# RGB_FPGA_Misc.net
KiCad netlist of a schematic drawn in Altium Designer
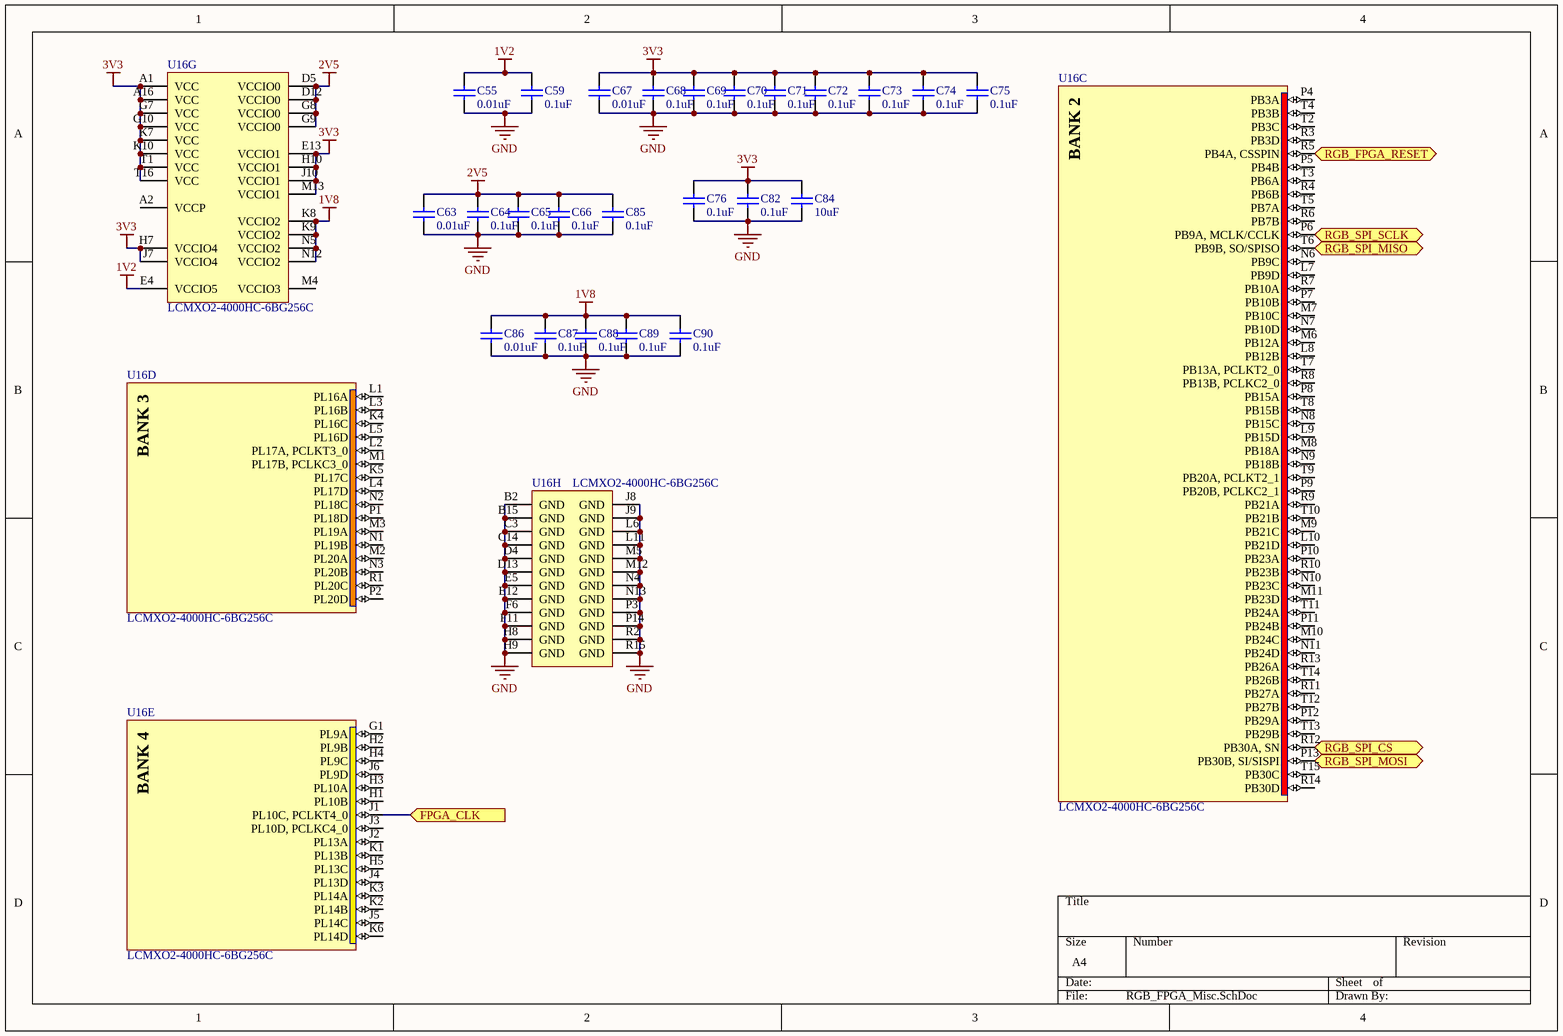
[diagram p0: RGB_FPGA_Misc.SchDoc]

(export (version "E")
  (design (tool "Eeschema 10.0.6"))
  (components
    (comp (ref "C55")
      (value "0.01uF")
      (footprint "0402C_M")
      (description "CAP CER 0.01uF 50V X7R 0402")
      (fields
        (field (name "MANUFACTURER") "Murata Electronics North America")
        (field (name "MANUFACTURER PART NUMBER") "GRM155R71H103KA88D")
      )
      (libsource (lib "KMTI-main") (part "GRM155R71H103KA88D"))
    )
    (comp (ref "C59")
      (value "GRM155R71C104KA88D")
      (footprint "0402C_M")
      (description "CAP CER 0.1UF 16V X7R 0402")
      (fields
        (field (name "MANUFACTURER") "Murata Electronics North America")
        (field (name "TOLERANCE") "±10%")
        (field (name "CAPACITANCE") "0.1uF")
      )
      (libsource (lib "KMTI-main") (part "GRM155R71C104KA88D"))
    )
    (comp (ref "C63")
      (value "0.01uF")
      (footprint "0402C_M")
      (description "CAP CER 0.01uF 50V X7R 0402")
      (fields
        (field (name "MANUFACTURER") "Murata Electronics North America")
        (field (name "MANUFACTURER PART NUMBER") "GRM155R71H103KA88D")
      )
      (libsource (lib "KMTI-main") (part "GRM155R71H103KA88D"))
    )
    (comp (ref "C64")
      (value "GRM155R71C104KA88D")
      (footprint "0402C_M")
      (description "CAP CER 0.1UF 16V X7R 0402")
      (fields
        (field (name "MANUFACTURER") "Murata Electronics North America")
        (field (name "TOLERANCE") "±10%")
        (field (name "CAPACITANCE") "0.1uF")
      )
      (libsource (lib "KMTI-main") (part "GRM155R71C104KA88D"))
    )
    (comp (ref "C65")
      (value "GRM155R71C104KA88D")
      (footprint "0402C_M")
      (description "CAP CER 0.1UF 16V X7R 0402")
      (fields
        (field (name "MANUFACTURER") "Murata Electronics North America")
        (field (name "TOLERANCE") "±10%")
        (field (name "CAPACITANCE") "0.1uF")
      )
      (libsource (lib "KMTI-main") (part "GRM155R71C104KA88D"))
    )
    (comp (ref "C66")
      (value "GRM155R71C104KA88D")
      (footprint "0402C_M")
      (description "CAP CER 0.1UF 16V X7R 0402")
      (fields
        (field (name "MANUFACTURER") "Murata Electronics North America")
        (field (name "TOLERANCE") "±10%")
        (field (name "CAPACITANCE") "0.1uF")
      )
      (libsource (lib "KMTI-main") (part "GRM155R71C104KA88D"))
    )
    (comp (ref "C67")
      (value "0.01uF")
      (footprint "0402C_M")
      (description "CAP CER 0.01uF 50V X7R 0402")
      (fields
        (field (name "MANUFACTURER") "Murata Electronics North America")
        (field (name "MANUFACTURER PART NUMBER") "GRM155R71H103KA88D")
      )
      (libsource (lib "KMTI-main") (part "GRM155R71H103KA88D"))
    )
    (comp (ref "C68")
      (value "GRM155R71C104KA88D")
      (footprint "0402C_M")
      (description "CAP CER 0.1UF 16V X7R 0402")
      (fields
        (field (name "MANUFACTURER") "Murata Electronics North America")
        (field (name "TOLERANCE") "±10%")
        (field (name "CAPACITANCE") "0.1uF")
      )
      (libsource (lib "KMTI-main") (part "GRM155R71C104KA88D"))
    )
    (comp (ref "C69")
      (value "GRM155R71C104KA88D")
      (footprint "0402C_M")
      (description "CAP CER 0.1UF 16V X7R 0402")
      (fields
        (field (name "MANUFACTURER") "Murata Electronics North America")
        (field (name "TOLERANCE") "±10%")
        (field (name "CAPACITANCE") "0.1uF")
      )
      (libsource (lib "KMTI-main") (part "GRM155R71C104KA88D"))
    )
    (comp (ref "C70")
      (value "GRM155R71C104KA88D")
      (footprint "0402C_M")
      (description "CAP CER 0.1UF 16V X7R 0402")
      (fields
        (field (name "MANUFACTURER") "Murata Electronics North America")
        (field (name "TOLERANCE") "±10%")
        (field (name "CAPACITANCE") "0.1uF")
      )
      (libsource (lib "KMTI-main") (part "GRM155R71C104KA88D"))
    )
    (comp (ref "C71")
      (value "GRM155R71C104KA88D")
      (footprint "0402C_M")
      (description "CAP CER 0.1UF 16V X7R 0402")
      (fields
        (field (name "MANUFACTURER") "Murata Electronics North America")
        (field (name "TOLERANCE") "±10%")
        (field (name "CAPACITANCE") "0.1uF")
      )
      (libsource (lib "KMTI-main") (part "GRM155R71C104KA88D"))
    )
    (comp (ref "C72")
      (value "GRM155R71C104KA88D")
      (footprint "0402C_M")
      (description "CAP CER 0.1UF 16V X7R 0402")
      (fields
        (field (name "MANUFACTURER") "Murata Electronics North America")
        (field (name "TOLERANCE") "±10%")
        (field (name "CAPACITANCE") "0.1uF")
      )
      (libsource (lib "KMTI-main") (part "GRM155R71C104KA88D"))
    )
    (comp (ref "C73")
      (value "GRM155R71C104KA88D")
      (footprint "0402C_M")
      (description "CAP CER 0.1UF 16V X7R 0402")
      (fields
        (field (name "MANUFACTURER") "Murata Electronics North America")
        (field (name "TOLERANCE") "±10%")
        (field (name "CAPACITANCE") "0.1uF")
      )
      (libsource (lib "KMTI-main") (part "GRM155R71C104KA88D"))
    )
    (comp (ref "C74")
      (value "GRM155R71C104KA88D")
      (footprint "0402C_M")
      (description "CAP CER 0.1UF 16V X7R 0402")
      (fields
        (field (name "MANUFACTURER") "Murata Electronics North America")
        (field (name "TOLERANCE") "±10%")
        (field (name "CAPACITANCE") "0.1uF")
      )
      (libsource (lib "KMTI-main") (part "GRM155R71C104KA88D"))
    )
    (comp (ref "C75")
      (value "GRM155R71C104KA88D")
      (footprint "0402C_M")
      (description "CAP CER 0.1UF 16V X7R 0402")
      (fields
        (field (name "MANUFACTURER") "Murata Electronics North America")
        (field (name "TOLERANCE") "±10%")
        (field (name "CAPACITANCE") "0.1uF")
      )
      (libsource (lib "KMTI-main") (part "GRM155R71C104KA88D"))
    )
    (comp (ref "C76")
      (value "GRM155R71C104KA88D")
      (footprint "0402C_M")
      (description "CAP CER 0.1UF 16V X7R 0402")
      (fields
        (field (name "MANUFACTURER") "Murata Electronics North America")
        (field (name "TOLERANCE") "±10%")
        (field (name "CAPACITANCE") "0.1uF")
      )
      (libsource (lib "KMTI-main") (part "GRM155R71C104KA88D"))
    )
    (comp (ref "C82")
      (value "GRM155R71C104KA88D")
      (footprint "0402C_M")
      (description "CAP CER 0.1UF 16V X7R 0402")
      (fields
        (field (name "MANUFACTURER") "Murata Electronics North America")
        (field (name "TOLERANCE") "±10%")
        (field (name "CAPACITANCE") "0.1uF")
      )
      (libsource (lib "KMTI-main") (part "GRM155R71C104KA88D"))
    )
    (comp (ref "C84")
      (value "10uF")
      (footprint "0603C_M")
      (description "CAP CER 10UF 6.3V X5R 0603")
      (fields
        (field (name "MANUFACTURER") "Murata Electronics North America")
        (field (name "MANUFACTURER PART NUMBER") "GRM188R60J106ME47D")
      )
      (libsource (lib "KMTI-main") (part "GRM188R60J106ME47D"))
    )
    (comp (ref "C85")
      (value "GRM155R71C104KA88D")
      (footprint "0402C_M")
      (description "CAP CER 0.1UF 16V X7R 0402")
      (fields
        (field (name "MANUFACTURER") "Murata Electronics North America")
        (field (name "TOLERANCE") "±10%")
        (field (name "CAPACITANCE") "0.1uF")
      )
      (libsource (lib "KMTI-main") (part "GRM155R71C104KA88D"))
    )
    (comp (ref "C86")
      (value "0.01uF")
      (footprint "0402C_M")
      (description "CAP CER 0.01uF 50V X7R 0402")
      (fields
        (field (name "MANUFACTURER") "Murata Electronics North America")
        (field (name "MANUFACTURER PART NUMBER") "GRM155R71H103KA88D")
      )
      (libsource (lib "KMTI-main") (part "GRM155R71H103KA88D"))
    )
    (comp (ref "C87")
      (value "GRM155R71C104KA88D")
      (footprint "0402C_M")
      (description "CAP CER 0.1UF 16V X7R 0402")
      (fields
        (field (name "MANUFACTURER") "Murata Electronics North America")
        (field (name "TOLERANCE") "±10%")
        (field (name "CAPACITANCE") "0.1uF")
      )
      (libsource (lib "KMTI-main") (part "GRM155R71C104KA88D"))
    )
    (comp (ref "C88")
      (value "GRM155R71C104KA88D")
      (footprint "0402C_M")
      (description "CAP CER 0.1UF 16V X7R 0402")
      (fields
        (field (name "MANUFACTURER") "Murata Electronics North America")
        (field (name "TOLERANCE") "±10%")
        (field (name "CAPACITANCE") "0.1uF")
      )
      (libsource (lib "KMTI-main") (part "GRM155R71C104KA88D"))
    )
    (comp (ref "C89")
      (value "GRM155R71C104KA88D")
      (footprint "0402C_M")
      (description "CAP CER 0.1UF 16V X7R 0402")
      (fields
        (field (name "MANUFACTURER") "Murata Electronics North America")
        (field (name "TOLERANCE") "±10%")
        (field (name "CAPACITANCE") "0.1uF")
      )
      (libsource (lib "KMTI-main") (part "GRM155R71C104KA88D"))
    )
    (comp (ref "C90")
      (value "GRM155R71C104KA88D")
      (footprint "0402C_M")
      (description "CAP CER 0.1UF 16V X7R 0402")
      (fields
        (field (name "MANUFACTURER") "Murata Electronics North America")
        (field (name "TOLERANCE") "±10%")
        (field (name "CAPACITANCE") "0.1uF")
      )
      (libsource (lib "KMTI-main") (part "GRM155R71C104KA88D"))
    )
    (comp (ref "U16")
      (value "LCMXO2-4000HC-6BG256C")
      (footprint "caBGA256")
      (libsource (lib "Altium Content Vault") (part "PLD-LTMXO2-4000-GA256"))
    )
  )
  (nets
    (net (code "1") (name "/FPGA_CLK") (class "Default")
      (node (ref "U16") (pin "J1") (pinfunction "PL10C,_PCLKT4_0_J1") (pintype "bidirectional"))
    )
    (net (code "2") (name "/RGB_FPGA_RESET") (class "Default")
      (node (ref "U16") (pin "R5") (pinfunction "PB4A,_CSSPIN_R5") (pintype "bidirectional"))
    )
    (net (code "3") (name "/RGB_SPI_CS") (class "Default")
      (node (ref "U16") (pin "R12") (pinfunction "PB30A,_SN_R12") (pintype "bidirectional"))
    )
    (net (code "4") (name "/RGB_SPI_MISO") (class "Default")
      (node (ref "U16") (pin "T6") (pinfunction "PB9B,_SO/SPISO_T6") (pintype "bidirectional"))
    )
    (net (code "5") (name "/RGB_SPI_MOSI") (class "Default")
      (node (ref "U16") (pin "P13") (pinfunction "PB30B,_SI/SISPI_P13") (pintype "bidirectional"))
    )
    (net (code "6") (name "/RGB_SPI_SCLK") (class "Default")
      (node (ref "U16") (pin "P6") (pinfunction "PB9A,_MCLK/CCLK_P6") (pintype "bidirectional"))
    )
    (net (code "7") (name "1V2") (class "Default")
      (node (ref "C55") (pin "2") (pinfunction "2_2") (pintype "passive"))
      (node (ref "C59") (pin "2") (pinfunction "2_2") (pintype "passive"))
      (node (ref "U16") (pin "E4") (pinfunction "VCCIO5_E4") (pintype "power_in"))
    )
    (net (code "8") (name "1V8") (class "Default")
      (node (ref "C86") (pin "2") (pinfunction "2_2") (pintype "passive"))
      (node (ref "C87") (pin "2") (pinfunction "2_2") (pintype "passive"))
      (node (ref "C88") (pin "2") (pinfunction "2_2") (pintype "passive"))
      (node (ref "C89") (pin "2") (pinfunction "2_2") (pintype "passive"))
      (node (ref "C90") (pin "2") (pinfunction "2_2") (pintype "passive"))
      (node (ref "U16") (pin "K8") (pinfunction "VCCIO2_K8") (pintype "power_in"))
      (node (ref "U16") (pin "K9") (pinfunction "VCCIO2_K9") (pintype "power_in"))
      (node (ref "U16") (pin "N12") (pinfunction "VCCIO2_N12") (pintype "power_in"))
      (node (ref "U16") (pin "N5") (pinfunction "VCCIO2_N5") (pintype "power_in"))
    )
    (net (code "9") (name "2V5") (class "Default")
      (node (ref "C63") (pin "2") (pinfunction "2_2") (pintype "passive"))
      (node (ref "C64") (pin "2") (pinfunction "2_2") (pintype "passive"))
      (node (ref "C65") (pin "2") (pinfunction "2_2") (pintype "passive"))
      (node (ref "C66") (pin "2") (pinfunction "2_2") (pintype "passive"))
      (node (ref "C85") (pin "2") (pinfunction "2_2") (pintype "passive"))
      (node (ref "U16") (pin "D12") (pinfunction "VCCIO0_D12") (pintype "power_in"))
      (node (ref "U16") (pin "D5") (pinfunction "VCCIO0_D5") (pintype "power_in"))
      (node (ref "U16") (pin "G8") (pinfunction "VCCIO0_G8") (pintype "power_in"))
      (node (ref "U16") (pin "G9") (pinfunction "VCCIO0_G9") (pintype "power_in"))
    )
    (net (code "10") (name "3V3") (class "Default")
      (node (ref "C67") (pin "2") (pinfunction "2_2") (pintype "passive"))
      (node (ref "C68") (pin "2") (pinfunction "2_2") (pintype "passive"))
      (node (ref "C69") (pin "2") (pinfunction "2_2") (pintype "passive"))
      (node (ref "C70") (pin "2") (pinfunction "2_2") (pintype "passive"))
      (node (ref "C71") (pin "2") (pinfunction "2_2") (pintype "passive"))
      (node (ref "C72") (pin "2") (pinfunction "2_2") (pintype "passive"))
      (node (ref "C73") (pin "2") (pinfunction "2_2") (pintype "passive"))
      (node (ref "C74") (pin "2") (pinfunction "2_2") (pintype "passive"))
      (node (ref "C75") (pin "2") (pinfunction "2_2") (pintype "passive"))
      (node (ref "C76") (pin "2") (pinfunction "2_2") (pintype "passive"))
      (node (ref "C82") (pin "2") (pinfunction "2_2") (pintype "passive"))
      (node (ref "C84") (pin "2") (pinfunction "2_2") (pintype "passive"))
      (node (ref "U16") (pin "A1") (pinfunction "VCC_A1") (pintype "power_in"))
      (node (ref "U16") (pin "A16") (pinfunction "VCC_A16") (pintype "power_in"))
      (node (ref "U16") (pin "E13") (pinfunction "VCCIO1_E13") (pintype "power_in"))
      (node (ref "U16") (pin "G10") (pinfunction "VCC_G10") (pintype "power_in"))
      (node (ref "U16") (pin "G7") (pinfunction "VCC_G7") (pintype "power_in"))
      (node (ref "U16") (pin "H10") (pinfunction "VCCIO1_H10") (pintype "power_in"))
      (node (ref "U16") (pin "H7") (pinfunction "VCCIO4_H7") (pintype "power_in"))
      (node (ref "U16") (pin "J10") (pinfunction "VCCIO1_J10") (pintype "power_in"))
      (node (ref "U16") (pin "J7") (pinfunction "VCCIO4_J7") (pintype "power_in"))
      (node (ref "U16") (pin "K10") (pinfunction "VCC_K10") (pintype "power_in"))
      (node (ref "U16") (pin "K7") (pinfunction "VCC_K7") (pintype "power_in"))
      (node (ref "U16") (pin "M13") (pinfunction "VCCIO1_M13") (pintype "power_in"))
      (node (ref "U16") (pin "T1") (pinfunction "VCC_T1") (pintype "power_in"))
      (node (ref "U16") (pin "T16") (pinfunction "VCC_T16") (pintype "power_in"))
    )
    (net (code "11") (name "GND") (class "Default")
      (node (ref "C55") (pin "1") (pinfunction "1_1") (pintype "passive"))
      (node (ref "C59") (pin "1") (pinfunction "1_1") (pintype "passive"))
      (node (ref "C63") (pin "1") (pinfunction "1_1") (pintype "passive"))
      (node (ref "C64") (pin "1") (pinfunction "1_1") (pintype "passive"))
      (node (ref "C65") (pin "1") (pinfunction "1_1") (pintype "passive"))
      (node (ref "C66") (pin "1") (pinfunction "1_1") (pintype "passive"))
      (node (ref "C67") (pin "1") (pinfunction "1_1") (pintype "passive"))
      (node (ref "C68") (pin "1") (pinfunction "1_1") (pintype "passive"))
      (node (ref "C69") (pin "1") (pinfunction "1_1") (pintype "passive"))
      (node (ref "C70") (pin "1") (pinfunction "1_1") (pintype "passive"))
      (node (ref "C71") (pin "1") (pinfunction "1_1") (pintype "passive"))
      (node (ref "C72") (pin "1") (pinfunction "1_1") (pintype "passive"))
      (node (ref "C73") (pin "1") (pinfunction "1_1") (pintype "passive"))
      (node (ref "C74") (pin "1") (pinfunction "1_1") (pintype "passive"))
      (node (ref "C75") (pin "1") (pinfunction "1_1") (pintype "passive"))
      (node (ref "C76") (pin "1") (pinfunction "1_1") (pintype "passive"))
      (node (ref "C82") (pin "1") (pinfunction "1_1") (pintype "passive"))
      (node (ref "C84") (pin "1") (pinfunction "1_1") (pintype "passive"))
      (node (ref "C85") (pin "1") (pinfunction "1_1") (pintype "passive"))
      (node (ref "C86") (pin "1") (pinfunction "1_1") (pintype "passive"))
      (node (ref "C87") (pin "1") (pinfunction "1_1") (pintype "passive"))
      (node (ref "C88") (pin "1") (pinfunction "1_1") (pintype "passive"))
      (node (ref "C89") (pin "1") (pinfunction "1_1") (pintype "passive"))
      (node (ref "C90") (pin "1") (pinfunction "1_1") (pintype "passive"))
      (node (ref "U16") (pin "B15") (pinfunction "GND_B15") (pintype "power_in"))
      (node (ref "U16") (pin "B2") (pinfunction "GND_B2") (pintype "power_in"))
      (node (ref "U16") (pin "C14") (pinfunction "GND_C14") (pintype "power_in"))
      (node (ref "U16") (pin "C3") (pinfunction "GND_C3") (pintype "power_in"))
      (node (ref "U16") (pin "D13") (pinfunction "GND_D13") (pintype "power_in"))
      (node (ref "U16") (pin "D4") (pinfunction "GND_D4") (pintype "power_in"))
      (node (ref "U16") (pin "E12") (pinfunction "GND_E12") (pintype "power_in"))
      (node (ref "U16") (pin "E5") (pinfunction "GND_E5") (pintype "power_in"))
      (node (ref "U16") (pin "F11") (pinfunction "GND_F11") (pintype "power_in"))
      (node (ref "U16") (pin "F6") (pinfunction "GND_F6") (pintype "power_in"))
      (node (ref "U16") (pin "H8") (pinfunction "GND_H8") (pintype "power_in"))
      (node (ref "U16") (pin "H9") (pinfunction "GND_H9") (pintype "power_in"))
      (node (ref "U16") (pin "J8") (pinfunction "GND_J8") (pintype "power_in"))
      (node (ref "U16") (pin "J9") (pinfunction "GND_J9") (pintype "power_in"))
      (node (ref "U16") (pin "L11") (pinfunction "GND_L11") (pintype "power_in"))
      (node (ref "U16") (pin "L6") (pinfunction "GND_L6") (pintype "power_in"))
      (node (ref "U16") (pin "M12") (pinfunction "GND_M12") (pintype "power_in"))
      (node (ref "U16") (pin "M5") (pinfunction "GND_M5") (pintype "power_in"))
      (node (ref "U16") (pin "N13") (pinfunction "GND_N13") (pintype "power_in"))
      (node (ref "U16") (pin "N4") (pinfunction "GND_N4") (pintype "power_in"))
      (node (ref "U16") (pin "P14") (pinfunction "GND_P14") (pintype "power_in"))
      (node (ref "U16") (pin "P3") (pinfunction "GND_P3") (pintype "power_in"))
      (node (ref "U16") (pin "R15") (pinfunction "GND_R15") (pintype "power_in"))
      (node (ref "U16") (pin "R2") (pinfunction "GND_R2") (pintype "power_in"))
    )
    (net (code "12") (name "unconnected-(U16C-PB3A-PadP4)") (class "Default")
      (node (ref "U16") (pin "P4") (pinfunction "PB3A_P4") (pintype "bidirectional"))
    )
    (net (code "13") (name "unconnected-(U16C-PB3B-PadT4)") (class "Default")
      (node (ref "U16") (pin "T4") (pinfunction "PB3B_T4") (pintype "bidirectional"))
    )
    (net (code "14") (name "unconnected-(U16C-PB3C-PadT2)") (class "Default")
      (node (ref "U16") (pin "T2") (pinfunction "PB3C_T2") (pintype "bidirectional"))
    )
    (net (code "15") (name "unconnected-(U16C-PB3D-PadR3)") (class "Default")
      (node (ref "U16") (pin "R3") (pinfunction "PB3D_R3") (pintype "bidirectional"))
    )
    (net (code "16") (name "unconnected-(U16C-PB4B-PadP5)") (class "Default")
      (node (ref "U16") (pin "P5") (pinfunction "PB4B_P5") (pintype "bidirectional"))
    )
    (net (code "17") (name "unconnected-(U16C-PB6A-PadT3)") (class "Default")
      (node (ref "U16") (pin "T3") (pinfunction "PB6A_T3") (pintype "bidirectional"))
    )
    (net (code "18") (name "unconnected-(U16C-PB6B-PadR4)") (class "Default")
      (node (ref "U16") (pin "R4") (pinfunction "PB6B_R4") (pintype "bidirectional"))
    )
    (net (code "19") (name "unconnected-(U16C-PB7A-PadT5)") (class "Default")
      (node (ref "U16") (pin "T5") (pinfunction "PB7A_T5") (pintype "bidirectional"))
    )
    (net (code "20") (name "unconnected-(U16C-PB7B-PadR6)") (class "Default")
      (node (ref "U16") (pin "R6") (pinfunction "PB7B_R6") (pintype "bidirectional"))
    )
    (net (code "21") (name "unconnected-(U16C-PB9C-PadN6)") (class "Default")
      (node (ref "U16") (pin "N6") (pinfunction "PB9C_N6") (pintype "bidirectional"))
    )
    (net (code "22") (name "unconnected-(U16C-PB9D-PadL7)") (class "Default")
      (node (ref "U16") (pin "L7") (pinfunction "PB9D_L7") (pintype "bidirectional"))
    )
    (net (code "23") (name "unconnected-(U16C-PB10A-PadR7)") (class "Default")
      (node (ref "U16") (pin "R7") (pinfunction "PB10A_R7") (pintype "bidirectional"))
    )
    (net (code "24") (name "unconnected-(U16C-PB10B-PadP7)") (class "Default")
      (node (ref "U16") (pin "P7") (pinfunction "PB10B_P7") (pintype "bidirectional"))
    )
    (net (code "25") (name "unconnected-(U16C-PB10C-PadM7)") (class "Default")
      (node (ref "U16") (pin "M7") (pinfunction "PB10C_M7") (pintype "bidirectional"))
    )
    (net (code "26") (name "unconnected-(U16C-PB10D-PadN7)") (class "Default")
      (node (ref "U16") (pin "N7") (pinfunction "PB10D_N7") (pintype "bidirectional"))
    )
    (net (code "27") (name "unconnected-(U16C-PB12A-PadM6)") (class "Default")
      (node (ref "U16") (pin "M6") (pinfunction "PB12A_M6") (pintype "bidirectional"))
    )
    (net (code "28") (name "unconnected-(U16C-PB12B-PadL8)") (class "Default")
      (node (ref "U16") (pin "L8") (pinfunction "PB12B_L8") (pintype "bidirectional"))
    )
    (net (code "29") (name "unconnected-(U16C-PB13A,_PCLKT2_0-PadT7)") (class "Default")
      (node (ref "U16") (pin "T7") (pinfunction "PB13A,_PCLKT2_0_T7") (pintype "bidirectional"))
    )
    (net (code "30") (name "unconnected-(U16C-PB13B,_PCLKC2_0-PadR8)") (class "Default")
      (node (ref "U16") (pin "R8") (pinfunction "PB13B,_PCLKC2_0_R8") (pintype "bidirectional"))
    )
    (net (code "31") (name "unconnected-(U16C-PB15A-PadP8)") (class "Default")
      (node (ref "U16") (pin "P8") (pinfunction "PB15A_P8") (pintype "bidirectional"))
    )
    (net (code "32") (name "unconnected-(U16C-PB15B-PadT8)") (class "Default")
      (node (ref "U16") (pin "T8") (pinfunction "PB15B_T8") (pintype "bidirectional"))
    )
    (net (code "33") (name "unconnected-(U16C-PB15C-PadN8)") (class "Default")
      (node (ref "U16") (pin "N8") (pinfunction "PB15C_N8") (pintype "bidirectional"))
    )
    (net (code "34") (name "unconnected-(U16C-PB15D-PadL9)") (class "Default")
      (node (ref "U16") (pin "L9") (pinfunction "PB15D_L9") (pintype "bidirectional"))
    )
    (net (code "35") (name "unconnected-(U16C-PB18A-PadM8)") (class "Default")
      (node (ref "U16") (pin "M8") (pinfunction "PB18A_M8") (pintype "bidirectional"))
    )
    (net (code "36") (name "unconnected-(U16C-PB18B-PadN9)") (class "Default")
      (node (ref "U16") (pin "N9") (pinfunction "PB18B_N9") (pintype "bidirectional"))
    )
    (net (code "37") (name "unconnected-(U16C-PB20A,_PCLKT2_1-PadT9)") (class "Default")
      (node (ref "U16") (pin "T9") (pinfunction "PB20A,_PCLKT2_1_T9") (pintype "bidirectional"))
    )
    (net (code "38") (name "unconnected-(U16C-PB20B,_PCLKC2_1-PadP9)") (class "Default")
      (node (ref "U16") (pin "P9") (pinfunction "PB20B,_PCLKC2_1_P9") (pintype "bidirectional"))
    )
    (net (code "39") (name "unconnected-(U16C-PB21A-PadR9)") (class "Default")
      (node (ref "U16") (pin "R9") (pinfunction "PB21A_R9") (pintype "bidirectional"))
    )
    (net (code "40") (name "unconnected-(U16C-PB21B-PadT10)") (class "Default")
      (node (ref "U16") (pin "T10") (pinfunction "PB21B_T10") (pintype "bidirectional"))
    )
    (net (code "41") (name "unconnected-(U16C-PB21C-PadM9)") (class "Default")
      (node (ref "U16") (pin "M9") (pinfunction "PB21C_M9") (pintype "bidirectional"))
    )
    (net (code "42") (name "unconnected-(U16C-PB21D-PadL10)") (class "Default")
      (node (ref "U16") (pin "L10") (pinfunction "PB21D_L10") (pintype "bidirectional"))
    )
    (net (code "43") (name "unconnected-(U16C-PB23A-PadP10)") (class "Default")
      (node (ref "U16") (pin "P10") (pinfunction "PB23A_P10") (pintype "bidirectional"))
    )
    (net (code "44") (name "unconnected-(U16C-PB23B-PadR10)") (class "Default")
      (node (ref "U16") (pin "R10") (pinfunction "PB23B_R10") (pintype "bidirectional"))
    )
    (net (code "45") (name "unconnected-(U16C-PB23C-PadN10)") (class "Default")
      (node (ref "U16") (pin "N10") (pinfunction "PB23C_N10") (pintype "bidirectional"))
    )
    (net (code "46") (name "unconnected-(U16C-PB23D-PadM11)") (class "Default")
      (node (ref "U16") (pin "M11") (pinfunction "PB23D_M11") (pintype "bidirectional"))
    )
    (net (code "47") (name "unconnected-(U16C-PB24A-PadT11)") (class "Default")
      (node (ref "U16") (pin "T11") (pinfunction "PB24A_T11") (pintype "bidirectional"))
    )
    (net (code "48") (name "unconnected-(U16C-PB24B-PadP11)") (class "Default")
      (node (ref "U16") (pin "P11") (pinfunction "PB24B_P11") (pintype "bidirectional"))
    )
    (net (code "49") (name "unconnected-(U16C-PB24C-PadM10)") (class "Default")
      (node (ref "U16") (pin "M10") (pinfunction "PB24C_M10") (pintype "bidirectional"))
    )
    (net (code "50") (name "unconnected-(U16C-PB24D-PadN11)") (class "Default")
      (node (ref "U16") (pin "N11") (pinfunction "PB24D_N11") (pintype "bidirectional"))
    )
    (net (code "51") (name "unconnected-(U16C-PB26A-PadR13)") (class "Default")
      (node (ref "U16") (pin "R13") (pinfunction "PB26A_R13") (pintype "bidirectional"))
    )
    (net (code "52") (name "unconnected-(U16C-PB26B-PadT14)") (class "Default")
      (node (ref "U16") (pin "T14") (pinfunction "PB26B_T14") (pintype "bidirectional"))
    )
    (net (code "53") (name "unconnected-(U16C-PB27A-PadR11)") (class "Default")
      (node (ref "U16") (pin "R11") (pinfunction "PB27A_R11") (pintype "bidirectional"))
    )
    (net (code "54") (name "unconnected-(U16C-PB27B-PadT12)") (class "Default")
      (node (ref "U16") (pin "T12") (pinfunction "PB27B_T12") (pintype "bidirectional"))
    )
    (net (code "55") (name "unconnected-(U16C-PB29A-PadP12)") (class "Default")
      (node (ref "U16") (pin "P12") (pinfunction "PB29A_P12") (pintype "bidirectional"))
    )
    (net (code "56") (name "unconnected-(U16C-PB29B-PadT13)") (class "Default")
      (node (ref "U16") (pin "T13") (pinfunction "PB29B_T13") (pintype "bidirectional"))
    )
    (net (code "57") (name "unconnected-(U16C-PB30C-PadT15)") (class "Default")
      (node (ref "U16") (pin "T15") (pinfunction "PB30C_T15") (pintype "bidirectional"))
    )
    (net (code "58") (name "unconnected-(U16C-PB30D-PadR14)") (class "Default")
      (node (ref "U16") (pin "R14") (pinfunction "PB30D_R14") (pintype "bidirectional"))
    )
    (net (code "59") (name "unconnected-(U16D-PL16A-PadL1)") (class "Default")
      (node (ref "U16") (pin "L1") (pinfunction "PL16A_L1") (pintype "bidirectional"))
    )
    (net (code "60") (name "unconnected-(U16D-PL16B-PadL3)") (class "Default")
      (node (ref "U16") (pin "L3") (pinfunction "PL16B_L3") (pintype "bidirectional"))
    )
    (net (code "61") (name "unconnected-(U16D-PL16C-PadK4)") (class "Default")
      (node (ref "U16") (pin "K4") (pinfunction "PL16C_K4") (pintype "bidirectional"))
    )
    (net (code "62") (name "unconnected-(U16D-PL16D-PadL5)") (class "Default")
      (node (ref "U16") (pin "L5") (pinfunction "PL16D_L5") (pintype "bidirectional"))
    )
    (net (code "63") (name "unconnected-(U16D-PL17A,_PCLKT3_0-PadL2)") (class "Default")
      (node (ref "U16") (pin "L2") (pinfunction "PL17A,_PCLKT3_0_L2") (pintype "bidirectional"))
    )
    (net (code "64") (name "unconnected-(U16D-PL17B,_PCLKC3_0-PadM1)") (class "Default")
      (node (ref "U16") (pin "M1") (pinfunction "PL17B,_PCLKC3_0_M1") (pintype "bidirectional"))
    )
    (net (code "65") (name "unconnected-(U16D-PL17C-PadK5)") (class "Default")
      (node (ref "U16") (pin "K5") (pinfunction "PL17C_K5") (pintype "bidirectional"))
    )
    (net (code "66") (name "unconnected-(U16D-PL17D-PadL4)") (class "Default")
      (node (ref "U16") (pin "L4") (pinfunction "PL17D_L4") (pintype "bidirectional"))
    )
    (net (code "67") (name "unconnected-(U16D-PL18C-PadN2)") (class "Default")
      (node (ref "U16") (pin "N2") (pinfunction "PL18C_N2") (pintype "bidirectional"))
    )
    (net (code "68") (name "unconnected-(U16D-PL18D-PadP1)") (class "Default")
      (node (ref "U16") (pin "P1") (pinfunction "PL18D_P1") (pintype "bidirectional"))
    )
    (net (code "69") (name "unconnected-(U16D-PL19A-PadM3)") (class "Default")
      (node (ref "U16") (pin "M3") (pinfunction "PL19A_M3") (pintype "bidirectional"))
    )
    (net (code "70") (name "unconnected-(U16D-PL19B-PadN1)") (class "Default")
      (node (ref "U16") (pin "N1") (pinfunction "PL19B_N1") (pintype "bidirectional"))
    )
    (net (code "71") (name "unconnected-(U16D-PL20A-PadM2)") (class "Default")
      (node (ref "U16") (pin "M2") (pinfunction "PL20A_M2") (pintype "bidirectional"))
    )
    (net (code "72") (name "unconnected-(U16D-PL20B-PadN3)") (class "Default")
      (node (ref "U16") (pin "N3") (pinfunction "PL20B_N3") (pintype "bidirectional"))
    )
    (net (code "73") (name "unconnected-(U16D-PL20C-PadR1)") (class "Default")
      (node (ref "U16") (pin "R1") (pinfunction "PL20C_R1") (pintype "bidirectional"))
    )
    (net (code "74") (name "unconnected-(U16D-PL20D-PadP2)") (class "Default")
      (node (ref "U16") (pin "P2") (pinfunction "PL20D_P2") (pintype "bidirectional"))
    )
    (net (code "75") (name "unconnected-(U16E-PL9A-PadG1)") (class "Default")
      (node (ref "U16") (pin "G1") (pinfunction "PL9A_G1") (pintype "bidirectional"))
    )
    (net (code "76") (name "unconnected-(U16E-PL9B-PadH2)") (class "Default")
      (node (ref "U16") (pin "H2") (pinfunction "PL9B_H2") (pintype "bidirectional"))
    )
    (net (code "77") (name "unconnected-(U16E-PL9C-PadH4)") (class "Default")
      (node (ref "U16") (pin "H4") (pinfunction "PL9C_H4") (pintype "bidirectional"))
    )
    (net (code "78") (name "unconnected-(U16E-PL9D-PadJ6)") (class "Default")
      (node (ref "U16") (pin "J6") (pinfunction "PL9D_J6") (pintype "bidirectional"))
    )
    (net (code "79") (name "unconnected-(U16E-PL10A-PadH3)") (class "Default")
      (node (ref "U16") (pin "H3") (pinfunction "PL10A_H3") (pintype "bidirectional"))
    )
    (net (code "80") (name "unconnected-(U16E-PL10B-PadH1)") (class "Default")
      (node (ref "U16") (pin "H1") (pinfunction "PL10B_H1") (pintype "bidirectional"))
    )
    (net (code "81") (name "unconnected-(U16E-PL10D,_PCLKC4_0-PadJ3)") (class "Default")
      (node (ref "U16") (pin "J3") (pinfunction "PL10D,_PCLKC4_0_J3") (pintype "bidirectional"))
    )
    (net (code "82") (name "unconnected-(U16E-PL13A-PadJ2)") (class "Default")
      (node (ref "U16") (pin "J2") (pinfunction "PL13A_J2") (pintype "bidirectional"))
    )
    (net (code "83") (name "unconnected-(U16E-PL13B-PadK1)") (class "Default")
      (node (ref "U16") (pin "K1") (pinfunction "PL13B_K1") (pintype "bidirectional"))
    )
    (net (code "84") (name "unconnected-(U16E-PL13C-PadH5)") (class "Default")
      (node (ref "U16") (pin "H5") (pinfunction "PL13C_H5") (pintype "bidirectional"))
    )
    (net (code "85") (name "unconnected-(U16E-PL13D-PadJ4)") (class "Default")
      (node (ref "U16") (pin "J4") (pinfunction "PL13D_J4") (pintype "bidirectional"))
    )
    (net (code "86") (name "unconnected-(U16E-PL14A-PadK3)") (class "Default")
      (node (ref "U16") (pin "K3") (pinfunction "PL14A_K3") (pintype "bidirectional"))
    )
    (net (code "87") (name "unconnected-(U16E-PL14B-PadK2)") (class "Default")
      (node (ref "U16") (pin "K2") (pinfunction "PL14B_K2") (pintype "bidirectional"))
    )
    (net (code "88") (name "unconnected-(U16E-PL14C-PadJ5)") (class "Default")
      (node (ref "U16") (pin "J5") (pinfunction "PL14C_J5") (pintype "bidirectional"))
    )
    (net (code "89") (name "unconnected-(U16E-PL14D-PadK6)") (class "Default")
      (node (ref "U16") (pin "K6") (pinfunction "PL14D_K6") (pintype "bidirectional"))
    )
    (net (code "90") (name "unconnected-(U16G-VCCIO3-PadM4)") (class "Default")
      (node (ref "U16") (pin "M4") (pinfunction "VCCIO3_M4") (pintype "power_in"))
    )
    (net (code "91") (name "unconnected-(U16G-VCCP-PadA2)") (class "Default")
      (node (ref "U16") (pin "A2") (pinfunction "VCCP_A2") (pintype "power_in"))
    )
  )
)
